# Esquem_tico.net
KiCad netlist of a schematic drawn in Altium Designer
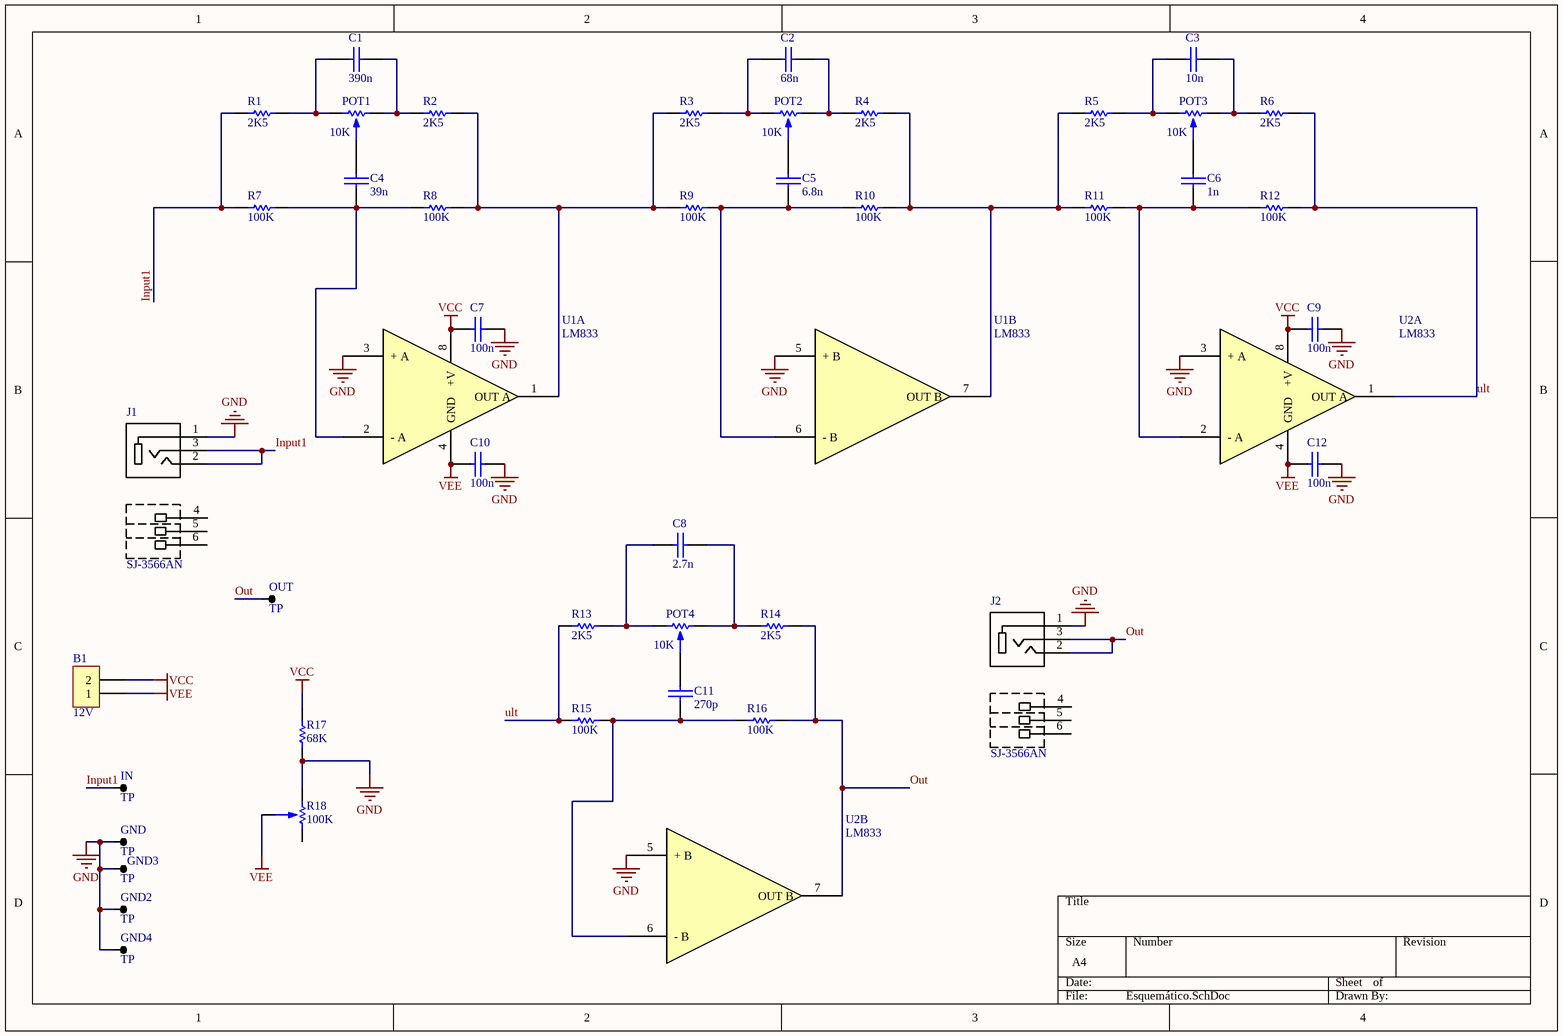
[diagram p0: Esquemático.SchDoc]

(export (version "E")
  (design (tool "Eeschema 10.0.6"))
  (components
    (comp (ref "B1") (value "12V") (footprint "BORNERA2") (libsource (lib "LIBEBAL") (part "BORNERA 2")))
    (comp (ref "C1") (value "390n") (footprint "CAP200") (libsource (lib "LIBEBAL") (part "CAP")))
    (comp (ref "C2") (value "68n") (footprint "CAP200") (libsource (lib "LIBEBAL") (part "CAP")))
    (comp (ref "C3") (value "10n") (footprint "CAP200") (libsource (lib "LIBEBAL") (part "CAP")))
    (comp (ref "C4") (value "39n") (footprint "CAP200") (libsource (lib "LIBEBAL") (part "CAP")))
    (comp (ref "C5") (value "6.8n") (footprint "CAP200") (libsource (lib "LIBEBAL") (part "CAP")))
    (comp (ref "C6") (value "1n") (footprint "CAP200") (libsource (lib "LIBEBAL") (part "CAP")))
    (comp (ref "C7") (value "100n") (footprint "CAP200") (libsource (lib "LIBEBAL") (part "CAP")))
    (comp (ref "C8") (value "2.7n") (footprint "CAP200") (libsource (lib "LIBEBAL") (part "CAP")))
    (comp (ref "C9") (value "100n") (footprint "CAP200") (libsource (lib "LIBEBAL") (part "CAP")))
    (comp (ref "C10") (value "100n") (footprint "CAP200") (libsource (lib "LIBEBAL") (part "CAP")))
    (comp (ref "C11") (value "270p") (footprint "CAP200") (libsource (lib "LIBEBAL") (part "CAP")))
    (comp (ref "C12") (value "100n") (footprint "CAP200") (libsource (lib "LIBEBAL") (part "CAP")))
    (comp (ref "GND") (value "TP") (footprint "TPTH") (libsource (lib "LIBEBAL") (part "TP")))
    (comp (ref "GND2") (value "TP") (footprint "TPTH") (libsource (lib "LIBEBAL") (part "TP")))
    (comp (ref "GND3") (value "TP") (footprint "TPTH") (libsource (lib "LIBEBAL") (part "TP")))
    (comp (ref "GND4") (value "TP") (footprint "TPTH") (libsource (lib "LIBEBAL") (part "TP")))
    (comp (ref "IN") (value "TP") (footprint "TPTH") (libsource (lib "LIBEBAL") (part "TP")))
    (comp (ref "J1")
      (value "SJ-3566AN")
      (footprint "*CUI_SJ-3566AN")
      (description "3.5 mm, Stereo, Right Angle, Through Hole, SPDT Switch, Audio Jack Connector")
      (fields (field (name "MF") "CUI Inc.") (field (name "DIGI-KEY_PART_NUMBER") "CP-SJ-3566AN-ND"))
      (libsource (lib "SJ-3566AN") (part "SJ-3566AN"))
    )
    (comp (ref "J2")
      (value "SJ-3566AN")
      (footprint "*CUI_SJ-3566AN")
      (description "3.5 mm, Stereo, Right Angle, Through Hole, SPDT Switch, Audio Jack Connector")
      (fields (field (name "MF") "CUI Inc.") (field (name "DIGI-KEY_PART_NUMBER") "CP-SJ-3566AN-ND"))
      (libsource (lib "SJ-3566AN") (part "SJ-3566AN"))
    )
    (comp (ref "OUT") (value "TP") (footprint "TPTH") (libsource (lib "LIBEBAL") (part "TP")))
    (comp (ref "POT1")
      (value "10K")
      (footprint "POTENCIOMETRO")
      (libsource (lib "LIBEBAL") (part "POTENCIOMETRO"))
    )
    (comp (ref "POT2")
      (value "10K")
      (footprint "POTENCIOMETRO")
      (libsource (lib "LIBEBAL") (part "POTENCIOMETRO"))
    )
    (comp (ref "POT3")
      (value "10K")
      (footprint "POTENCIOMETRO")
      (libsource (lib "LIBEBAL") (part "POTENCIOMETRO"))
    )
    (comp (ref "POT4")
      (value "10K")
      (footprint "POTENCIOMETRO")
      (libsource (lib "LIBEBAL") (part "POTENCIOMETRO"))
    )
    (comp (ref "R1") (value "2K5") (footprint "RES400") (libsource (lib "LIBEBAL") (part "RES")))
    (comp (ref "R2") (value "2K5") (footprint "RES400") (libsource (lib "LIBEBAL") (part "RES")))
    (comp (ref "R3") (value "2K5") (footprint "RES400") (libsource (lib "LIBEBAL") (part "RES")))
    (comp (ref "R4") (value "2K5") (footprint "RES400") (libsource (lib "LIBEBAL") (part "RES")))
    (comp (ref "R5") (value "2K5") (footprint "RES400") (libsource (lib "LIBEBAL") (part "RES")))
    (comp (ref "R6") (value "2K5") (footprint "RES400") (libsource (lib "LIBEBAL") (part "RES")))
    (comp (ref "R7") (value "100K") (footprint "RES400") (libsource (lib "LIBEBAL") (part "RES")))
    (comp (ref "R8") (value "100K") (footprint "RES400") (libsource (lib "LIBEBAL") (part "RES")))
    (comp (ref "R9") (value "100K") (footprint "RES400") (libsource (lib "LIBEBAL") (part "RES")))
    (comp (ref "R10") (value "100K") (footprint "RES400") (libsource (lib "LIBEBAL") (part "RES")))
    (comp (ref "R11") (value "100K") (footprint "RES400") (libsource (lib "LIBEBAL") (part "RES")))
    (comp (ref "R12") (value "100K") (footprint "RES400") (libsource (lib "LIBEBAL") (part "RES")))
    (comp (ref "R13") (value "2K5") (footprint "RES400") (libsource (lib "LIBEBAL") (part "RES")))
    (comp (ref "R14") (value "2K5") (footprint "RES400") (libsource (lib "LIBEBAL") (part "RES")))
    (comp (ref "R15") (value "100K") (footprint "RES400") (libsource (lib "LIBEBAL") (part "RES")))
    (comp (ref "R16") (value "100K") (footprint "RES400") (libsource (lib "LIBEBAL") (part "RES")))
    (comp (ref "R17") (value "68K") (footprint "RES400") (libsource (lib "LIBEBAL") (part "RES")))
    (comp (ref "R18") (value "100K") (footprint "PRESET H") (libsource (lib "LIBEBAL") (part "PRESET")))
    (comp (ref "U1")
      (value "LM833")
      (footprint "DIP8")
      (description "Dual Audio Operational Amplifier")
      (libsource (lib "LIBEBAL") (part "LM833"))
    )
    (comp (ref "U2")
      (value "LM833")
      (footprint "DIP8")
      (description "Dual Audio Operational Amplifier")
      (libsource (lib "LIBEBAL") (part "LM833"))
    )
  )
  (nets
    (net (code "1") (name "/Input1") (class "Default")
      (node (ref "IN") (pin "1") (pinfunction "1_1") (pintype "passive"))
      (node (ref "J1") (pin "2") (pinfunction "2_2") (pintype "passive"))
      (node (ref "J1") (pin "3") (pinfunction "3_3") (pintype "passive"))
      (node (ref "R1") (pin "1") (pinfunction "1_1") (pintype "passive"))
      (node (ref "R7") (pin "1") (pinfunction "1_1") (pintype "passive"))
    )
    (net (code "2") (name "/Out") (class "Default")
      (node (ref "J2") (pin "2") (pinfunction "2_2") (pintype "passive"))
      (node (ref "J2") (pin "3") (pinfunction "3_3") (pintype "passive"))
      (node (ref "OUT") (pin "1") (pinfunction "1_1") (pintype "passive"))
      (node (ref "R14") (pin "2") (pinfunction "2_2") (pintype "passive"))
      (node (ref "R16") (pin "2") (pinfunction "2_2") (pintype "passive"))
      (node (ref "U2") (pin "7") (pinfunction "OUT_B_7") (pintype "passive"))
    )
    (net (code "3") (name "/ult") (class "Default")
      (node (ref "R12") (pin "2") (pinfunction "2_2") (pintype "passive"))
      (node (ref "R13") (pin "1") (pinfunction "1_1") (pintype "passive"))
      (node (ref "R15") (pin "1") (pinfunction "1_1") (pintype "passive"))
      (node (ref "R6") (pin "2") (pinfunction "2_2") (pintype "passive"))
      (node (ref "U2") (pin "1") (pinfunction "OUT_A_1") (pintype "passive"))
    )
    (net (code "4") (name "GND") (class "Default")
      (node (ref "C10") (pin "2") (pinfunction "2_2") (pintype "passive"))
      (node (ref "C12") (pin "2") (pinfunction "2_2") (pintype "passive"))
      (node (ref "C7") (pin "2") (pinfunction "2_2") (pintype "passive"))
      (node (ref "C9") (pin "2") (pinfunction "2_2") (pintype "passive"))
      (node (ref "GND") (pin "1") (pinfunction "1_1") (pintype "passive"))
      (node (ref "GND2") (pin "1") (pinfunction "1_1") (pintype "passive"))
      (node (ref "GND3") (pin "1") (pinfunction "1_1") (pintype "passive"))
      (node (ref "GND4") (pin "1") (pinfunction "1_1") (pintype "passive"))
      (node (ref "J1") (pin "1") (pinfunction "1_1") (pintype "passive"))
      (node (ref "J2") (pin "1") (pinfunction "1_1") (pintype "passive"))
      (node (ref "R17") (pin "1") (pinfunction "1_1") (pintype "passive"))
      (node (ref "R18") (pin "3") (pinfunction "3_3") (pintype "passive"))
      (node (ref "U1") (pin "3") (pinfunction "+_A_3") (pintype "passive"))
      (node (ref "U1") (pin "5") (pinfunction "+_B_5") (pintype "passive"))
      (node (ref "U2") (pin "3") (pinfunction "+_A_3") (pintype "passive"))
      (node (ref "U2") (pin "5") (pinfunction "+_B_5") (pintype "passive"))
    )
    (net (code "5") (name "Net-(C1-Pad1)") (class "Default")
      (node (ref "C1") (pin "1") (pinfunction "1_1") (pintype "passive"))
      (node (ref "POT1") (pin "3") (pinfunction "3_3") (pintype "passive"))
      (node (ref "R1") (pin "2") (pinfunction "2_2") (pintype "passive"))
    )
    (net (code "6") (name "Net-(C1-Pad2)") (class "Default")
      (node (ref "C1") (pin "2") (pinfunction "2_2") (pintype "passive"))
      (node (ref "POT1") (pin "1") (pinfunction "1_1") (pintype "passive"))
      (node (ref "R2") (pin "1") (pinfunction "1_1") (pintype "passive"))
    )
    (net (code "7") (name "Net-(C2-Pad1)") (class "Default")
      (node (ref "C2") (pin "1") (pinfunction "1_1") (pintype "passive"))
      (node (ref "POT2") (pin "3") (pinfunction "3_3") (pintype "passive"))
      (node (ref "R3") (pin "2") (pinfunction "2_2") (pintype "passive"))
    )
    (net (code "8") (name "Net-(C2-Pad2)") (class "Default")
      (node (ref "C2") (pin "2") (pinfunction "2_2") (pintype "passive"))
      (node (ref "POT2") (pin "1") (pinfunction "1_1") (pintype "passive"))
      (node (ref "R4") (pin "1") (pinfunction "1_1") (pintype "passive"))
    )
    (net (code "9") (name "Net-(C3-Pad1)") (class "Default")
      (node (ref "C3") (pin "1") (pinfunction "1_1") (pintype "passive"))
      (node (ref "POT3") (pin "3") (pinfunction "3_3") (pintype "passive"))
      (node (ref "R5") (pin "2") (pinfunction "2_2") (pintype "passive"))
    )
    (net (code "10") (name "Net-(C3-Pad2)") (class "Default")
      (node (ref "C3") (pin "2") (pinfunction "2_2") (pintype "passive"))
      (node (ref "POT3") (pin "1") (pinfunction "1_1") (pintype "passive"))
      (node (ref "R6") (pin "1") (pinfunction "1_1") (pintype "passive"))
    )
    (net (code "11") (name "Net-(C4-Pad1)") (class "Default")
      (node (ref "C4") (pin "1") (pinfunction "1_1") (pintype "passive"))
      (node (ref "POT1") (pin "2") (pinfunction "2_2") (pintype "passive"))
    )
    (net (code "12") (name "Net-(C5-Pad1)") (class "Default")
      (node (ref "C5") (pin "1") (pinfunction "1_1") (pintype "passive"))
      (node (ref "POT2") (pin "2") (pinfunction "2_2") (pintype "passive"))
    )
    (net (code "13") (name "Net-(C6-Pad1)") (class "Default")
      (node (ref "C6") (pin "1") (pinfunction "1_1") (pintype "passive"))
      (node (ref "POT3") (pin "2") (pinfunction "2_2") (pintype "passive"))
    )
    (net (code "14") (name "Net-(C8-Pad1)") (class "Default")
      (node (ref "C8") (pin "1") (pinfunction "1_1") (pintype "passive"))
      (node (ref "POT4") (pin "3") (pinfunction "3_3") (pintype "passive"))
      (node (ref "R13") (pin "2") (pinfunction "2_2") (pintype "passive"))
    )
    (net (code "15") (name "Net-(C8-Pad2)") (class "Default")
      (node (ref "C8") (pin "2") (pinfunction "2_2") (pintype "passive"))
      (node (ref "POT4") (pin "1") (pinfunction "1_1") (pintype "passive"))
      (node (ref "R14") (pin "1") (pinfunction "1_1") (pintype "passive"))
    )
    (net (code "16") (name "Net-(C11-Pad1)") (class "Default")
      (node (ref "C11") (pin "1") (pinfunction "1_1") (pintype "passive"))
      (node (ref "POT4") (pin "2") (pinfunction "2_2") (pintype "passive"))
    )
    (net (code "17") (name "Net-(U1A--_A)") (class "Default")
      (node (ref "C4") (pin "2") (pinfunction "2_2") (pintype "passive"))
      (node (ref "R7") (pin "2") (pinfunction "2_2") (pintype "passive"))
      (node (ref "R8") (pin "1") (pinfunction "1_1") (pintype "passive"))
      (node (ref "U1") (pin "2") (pinfunction "-_A_2") (pintype "passive"))
    )
    (net (code "18") (name "Net-(U1A-OUT_A)") (class "Default")
      (node (ref "R2") (pin "2") (pinfunction "2_2") (pintype "passive"))
      (node (ref "R3") (pin "1") (pinfunction "1_1") (pintype "passive"))
      (node (ref "R8") (pin "2") (pinfunction "2_2") (pintype "passive"))
      (node (ref "R9") (pin "1") (pinfunction "1_1") (pintype "passive"))
      (node (ref "U1") (pin "1") (pinfunction "OUT_A_1") (pintype "passive"))
    )
    (net (code "19") (name "Net-(U1B--_B)") (class "Default")
      (node (ref "C5") (pin "2") (pinfunction "2_2") (pintype "passive"))
      (node (ref "R10") (pin "1") (pinfunction "1_1") (pintype "passive"))
      (node (ref "R9") (pin "2") (pinfunction "2_2") (pintype "passive"))
      (node (ref "U1") (pin "6") (pinfunction "-_B_6") (pintype "passive"))
    )
    (net (code "20") (name "Net-(U1B-OUT_B)") (class "Default")
      (node (ref "R10") (pin "2") (pinfunction "2_2") (pintype "passive"))
      (node (ref "R11") (pin "1") (pinfunction "1_1") (pintype "passive"))
      (node (ref "R4") (pin "2") (pinfunction "2_2") (pintype "passive"))
      (node (ref "R5") (pin "1") (pinfunction "1_1") (pintype "passive"))
      (node (ref "U1") (pin "7") (pinfunction "OUT_B_7") (pintype "passive"))
    )
    (net (code "21") (name "Net-(U2A--_A)") (class "Default")
      (node (ref "C6") (pin "2") (pinfunction "2_2") (pintype "passive"))
      (node (ref "R11") (pin "2") (pinfunction "2_2") (pintype "passive"))
      (node (ref "R12") (pin "1") (pinfunction "1_1") (pintype "passive"))
      (node (ref "U2") (pin "2") (pinfunction "-_A_2") (pintype "passive"))
    )
    (net (code "22") (name "Net-(U2B--_B)") (class "Default")
      (node (ref "C11") (pin "2") (pinfunction "2_2") (pintype "passive"))
      (node (ref "R15") (pin "2") (pinfunction "2_2") (pintype "passive"))
      (node (ref "R16") (pin "1") (pinfunction "1_1") (pintype "passive"))
      (node (ref "U2") (pin "6") (pinfunction "-_B_6") (pintype "passive"))
    )
    (net (code "23") (name "VCC") (class "Default")
      (node (ref "B1") (pin "2") (pinfunction "2_2") (pintype "passive"))
      (node (ref "C7") (pin "1") (pinfunction "1_1") (pintype "passive"))
      (node (ref "C9") (pin "1") (pinfunction "1_1") (pintype "passive"))
      (node (ref "R17") (pin "2") (pinfunction "2_2") (pintype "passive"))
      (node (ref "U1") (pin "8") (pinfunction "+V_8") (pintype "passive"))
      (node (ref "U2") (pin "8") (pinfunction "+V_8") (pintype "passive"))
    )
    (net (code "24") (name "VEE") (class "Default")
      (node (ref "B1") (pin "1") (pinfunction "1_1") (pintype "passive"))
      (node (ref "C10") (pin "1") (pinfunction "1_1") (pintype "passive"))
      (node (ref "C12") (pin "1") (pinfunction "1_1") (pintype "passive"))
      (node (ref "R18") (pin "2") (pinfunction "2_2") (pintype "passive"))
      (node (ref "U1") (pin "4") (pinfunction "GND_4") (pintype "passive"))
      (node (ref "U2") (pin "4") (pinfunction "GND_4") (pintype "passive"))
    )
    (net (code "25") (name "unconnected-(J1-Pad4)") (class "Default")
      (node (ref "J1") (pin "4") (pinfunction "4_4") (pintype "passive"))
    )
    (net (code "26") (name "unconnected-(J1-Pad5)") (class "Default")
      (node (ref "J1") (pin "5") (pinfunction "5_5") (pintype "passive"))
    )
    (net (code "27") (name "unconnected-(J1-Pad6)") (class "Default")
      (node (ref "J1") (pin "6") (pinfunction "6_6") (pintype "passive"))
    )
    (net (code "28") (name "unconnected-(J2-Pad4)") (class "Default")
      (node (ref "J2") (pin "4") (pinfunction "4_4") (pintype "passive"))
    )
    (net (code "29") (name "unconnected-(J2-Pad5)") (class "Default")
      (node (ref "J2") (pin "5") (pinfunction "5_5") (pintype "passive"))
    )
    (net (code "30") (name "unconnected-(J2-Pad6)") (class "Default")
      (node (ref "J2") (pin "6") (pinfunction "6_6") (pintype "passive"))
    )
    (net (code "31") (name "unconnected-(R18-Pad1)") (class "Default")
      (node (ref "R18") (pin "1") (pinfunction "1_1") (pintype "passive"))
    )
  )
)
